# Connectors.net
KiCad netlist of a schematic drawn in Altium Designer
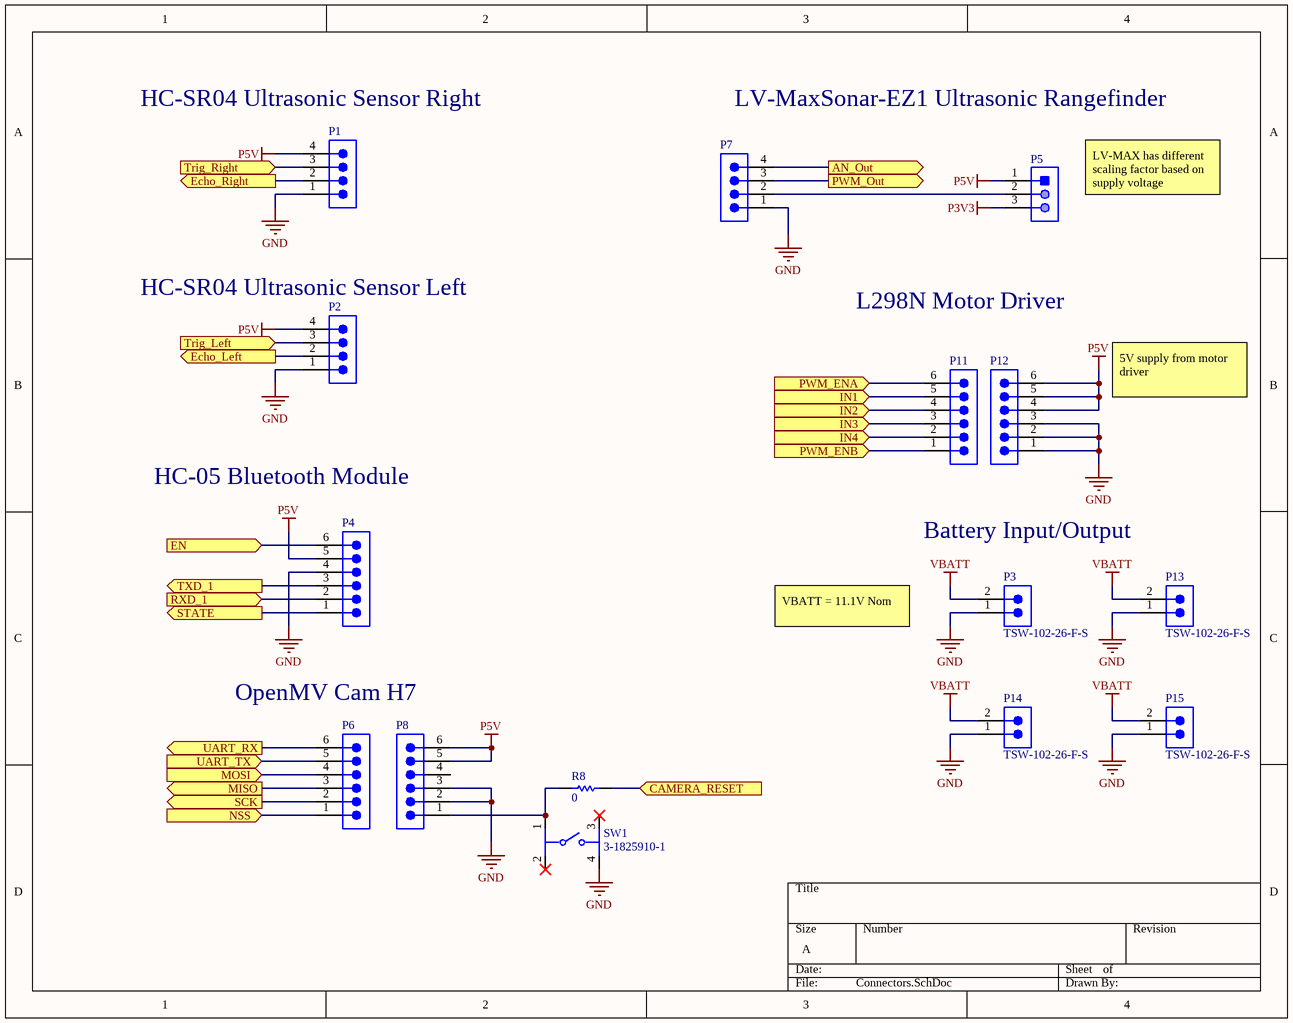
[diagram p0: Connectors.SchDoc]

(export (version "E")
  (design (tool "Eeschema 10.0.6"))
  (components
    (comp (ref "P1")
      (value "TSW-104-08-T-S")
      (footprint "SMTC-TSW-104-08-X-S")
      (description "0.025\" SQ Post Header, Through-hole, Vertical, -55 to 105 degC, 2.54 mm Pitch, 4-Pin, Male, RoHS")
      (fields (field (name "MANUFACTURER") "Samtec"))
      (libsource (lib "Altium Content Vault") (part "SMTC-TSW-104-08-X-S"))
    )
    (comp (ref "P2")
      (value "TSW-104-08-T-S")
      (footprint "SMTC-TSW-104-08-X-S")
      (description "0.025\" SQ Post Header, Through-hole, Vertical, -55 to 105 degC, 2.54 mm Pitch, 4-Pin, Male, RoHS")
      (fields (field (name "MANUFACTURER") "Samtec"))
      (libsource (lib "Altium Content Vault") (part "SMTC-TSW-104-08-X-S"))
    )
    (comp (ref "P3")
      (value "TSW-102-26-F-S")
      (footprint "SMTC-TSW-102-26-XX-S")
      (description "Headers & Wire Housings Classic PCB Header Strips, 0.100 pitch")
      (libsource (lib "University of California Riverside - FSAE") (part "SMTC-TSW-102-X-X-S-X"))
    )
    (comp (ref "P4")
      (value "TSW-106-23-G-S")
      (footprint "SMTC-TSW-106-23-X-S")
      (description "0.025\" SQ Post Header, Through-hole, Vertical, -55 to 125 degC, 2.54 mm Pitch, 6-Pin, Male, RoHS")
      (fields (field (name "MANUFACTURER") "Samtec"))
      (libsource (lib "Altium Content Vault") (part "SMTC-TSW-106-X-X-S-X"))
    )
    (comp (ref "P5")
      (value "87224-3")
      (footprint "TECO-87224-3_V")
      (fields (field (name "MANUFACTURER") "TE Connectivity"))
      (libsource (lib "Altium Content Vault") (part "CN-1P-M-R3"))
    )
    (comp (ref "P6")
      (value "TSW-106-23-G-S")
      (footprint "SMTC-TSW-106-23-X-S")
      (description "0.025\" SQ Post Header, Through-hole, Vertical, -55 to 125 degC, 2.54 mm Pitch, 6-Pin, Male, RoHS")
      (fields (field (name "MANUFACTURER") "Samtec"))
      (libsource (lib "Altium Content Vault") (part "SMTC-TSW-106-X-X-S-X"))
    )
    (comp (ref "P7")
      (value "TSW-104-08-T-S")
      (footprint "SMTC-TSW-104-08-X-S")
      (description "0.025\" SQ Post Header, Through-hole, Vertical, -55 to 105 degC, 2.54 mm Pitch, 4-Pin, Male, RoHS")
      (fields (field (name "MANUFACTURER") "Samtec"))
      (libsource (lib "Altium Content Vault") (part "SMTC-TSW-104-08-X-S"))
    )
    (comp (ref "P8")
      (value "TSW-106-23-G-S")
      (footprint "SMTC-TSW-106-23-X-S")
      (description "0.025\" SQ Post Header, Through-hole, Vertical, -55 to 125 degC, 2.54 mm Pitch, 6-Pin, Male, RoHS")
      (fields (field (name "MANUFACTURER") "Samtec"))
      (libsource (lib "Altium Content Vault") (part "SMTC-TSW-106-X-X-S-X"))
    )
    (comp (ref "P11")
      (value "TSW-106-23-G-S")
      (footprint "SMTC-TSW-106-23-X-S")
      (description "0.025\" SQ Post Header, Through-hole, Vertical, -55 to 125 degC, 2.54 mm Pitch, 6-Pin, Male, RoHS")
      (fields (field (name "MANUFACTURER") "Samtec"))
      (libsource (lib "Altium Content Vault") (part "SMTC-TSW-106-X-X-S-X"))
    )
    (comp (ref "P12")
      (value "TSW-106-23-G-S")
      (footprint "SMTC-TSW-106-23-X-S")
      (description "0.025\" SQ Post Header, Through-hole, Vertical, -55 to 125 degC, 2.54 mm Pitch, 6-Pin, Male, RoHS")
      (fields (field (name "MANUFACTURER") "Samtec"))
      (libsource (lib "Altium Content Vault") (part "SMTC-TSW-106-X-X-S-X"))
    )
    (comp (ref "P13")
      (value "TSW-102-26-F-S")
      (footprint "SMTC-TSW-102-26-XX-S")
      (description "Headers & Wire Housings Classic PCB Header Strips, 0.100 pitch")
      (libsource (lib "University of California Riverside - FSAE") (part "SMTC-TSW-102-X-X-S-X"))
    )
    (comp (ref "P14")
      (value "TSW-102-26-F-S")
      (footprint "SMTC-TSW-102-26-XX-S")
      (description "Headers & Wire Housings Classic PCB Header Strips, 0.100 pitch")
      (libsource (lib "University of California Riverside - FSAE") (part "SMTC-TSW-102-X-X-S-X"))
    )
    (comp (ref "P15")
      (value "TSW-102-26-F-S")
      (footprint "SMTC-TSW-102-26-XX-S")
      (description "Headers & Wire Housings Classic PCB Header Strips, 0.100 pitch")
      (libsource (lib "University of California Riverside - FSAE") (part "SMTC-TSW-102-X-X-S-X"))
    )
    (comp (ref "R8")
      (value "0")
      (footprint "RESC3216X60X45ML15T20")
      (description "Chip Resistor, 0 Ohm, +/- 5%, 0.25 W, -55 to 155 degC, 1206 (3216 Metric)")
      (fields (field (name "POWER") "250mW") (field (name "TOLERANCE") "5%"))
      (libsource (lib "University of California Riverside - FSAE") (part "RES-2"))
    )
    (comp (ref "SW1")
      (value "3-1825910-1")
      (footprint "FP-3-1825910-1-MFG")
      (description "Switch Tactile OFF (ON) SPST Round Button PC Pins 0.05A 24VDC 100000Cycles 1.57N Thru-Hole")
      (fields (field (name "MANUFACTURER") "TE Connectivity"))
      (libsource (lib "Altium Content Vault") (part "b8895f3f4cefb76e1819d2863dba89b"))
    )
  )
  (nets
    (net (code "1") (name "/AN_Out") (class "Default")
      (node (ref "P7") (pin "4") (pinfunction "4_4") (pintype "passive"))
    )
    (net (code "2") (name "/CAMERA_RESET") (class "Default")
      (node (ref "R8") (pin "2") (pinfunction "2_2") (pintype "passive"))
    )
    (net (code "3") (name "/EN") (class "Default")
      (node (ref "P4") (pin "6") (pinfunction "6_6") (pintype "passive"))
    )
    (net (code "4") (name "/Echo_Left") (class "Default")
      (node (ref "P2") (pin "2") (pinfunction "2_2") (pintype "passive"))
    )
    (net (code "5") (name "/Echo_Right") (class "Default")
      (node (ref "P1") (pin "2") (pinfunction "2_2") (pintype "passive"))
    )
    (net (code "6") (name "/IN1") (class "Default")
      (node (ref "P11") (pin "5") (pinfunction "5_5") (pintype "passive"))
    )
    (net (code "7") (name "/IN2") (class "Default")
      (node (ref "P11") (pin "4") (pinfunction "4_4") (pintype "passive"))
    )
    (net (code "8") (name "/IN3") (class "Default")
      (node (ref "P11") (pin "3") (pinfunction "3_3") (pintype "passive"))
    )
    (net (code "9") (name "/IN4") (class "Default")
      (node (ref "P11") (pin "2") (pinfunction "2_2") (pintype "passive"))
    )
    (net (code "10") (name "/MISO") (class "Default")
      (node (ref "P6") (pin "3") (pinfunction "3_3") (pintype "passive"))
    )
    (net (code "11") (name "/MOSI") (class "Default")
      (node (ref "P6") (pin "4") (pinfunction "4_4") (pintype "passive"))
    )
    (net (code "12") (name "/NSS") (class "Default")
      (node (ref "P6") (pin "1") (pinfunction "1_1") (pintype "passive"))
    )
    (net (code "13") (name "/PWM_ENA") (class "Default")
      (node (ref "P11") (pin "6") (pinfunction "6_6") (pintype "passive"))
    )
    (net (code "14") (name "/PWM_ENB") (class "Default")
      (node (ref "P11") (pin "1") (pinfunction "1_1") (pintype "passive"))
    )
    (net (code "15") (name "/PWM_Out") (class "Default")
      (node (ref "P7") (pin "3") (pinfunction "3_3") (pintype "passive"))
    )
    (net (code "16") (name "/RXD_1") (class "Default")
      (node (ref "P4") (pin "2") (pinfunction "2_2") (pintype "passive"))
    )
    (net (code "17") (name "/SCK") (class "Default")
      (node (ref "P6") (pin "2") (pinfunction "2_2") (pintype "passive"))
    )
    (net (code "18") (name "/STATE") (class "Default")
      (node (ref "P4") (pin "1") (pinfunction "1_1") (pintype "passive"))
    )
    (net (code "19") (name "/TXD_1") (class "Default")
      (node (ref "P4") (pin "3") (pinfunction "3_3") (pintype "passive"))
    )
    (net (code "20") (name "/Trig_Left") (class "Default")
      (node (ref "P2") (pin "3") (pinfunction "3_3") (pintype "passive"))
    )
    (net (code "21") (name "/Trig_Right") (class "Default")
      (node (ref "P1") (pin "3") (pinfunction "3_3") (pintype "passive"))
    )
    (net (code "22") (name "/UART_RX") (class "Default")
      (node (ref "P6") (pin "6") (pinfunction "6_6") (pintype "passive"))
    )
    (net (code "23") (name "/UART_TX") (class "Default")
      (node (ref "P6") (pin "5") (pinfunction "5_5") (pintype "passive"))
    )
    (net (code "24") (name "GND") (class "Default")
      (node (ref "P1") (pin "1") (pinfunction "1_1") (pintype "passive"))
      (node (ref "P12") (pin "1") (pinfunction "1_1") (pintype "passive"))
      (node (ref "P12") (pin "2") (pinfunction "2_2") (pintype "passive"))
      (node (ref "P12") (pin "3") (pinfunction "3_3") (pintype "passive"))
      (node (ref "P13") (pin "1") (pinfunction "1_1") (pintype "passive"))
      (node (ref "P14") (pin "1") (pinfunction "1_1") (pintype "passive"))
      (node (ref "P15") (pin "1") (pinfunction "1_1") (pintype "passive"))
      (node (ref "P2") (pin "1") (pinfunction "1_1") (pintype "passive"))
      (node (ref "P3") (pin "1") (pinfunction "1_1") (pintype "passive"))
      (node (ref "P4") (pin "4") (pinfunction "4_4") (pintype "passive"))
      (node (ref "P7") (pin "1") (pinfunction "1_1") (pintype "passive"))
      (node (ref "P8") (pin "2") (pinfunction "2_2") (pintype "passive"))
      (node (ref "P8") (pin "3") (pinfunction "3_3") (pintype "passive"))
      (node (ref "SW1") (pin "4") (pinfunction "4_4") (pintype "passive"))
    )
    (net (code "25") (name "Net-(P5-Pad2)") (class "Default")
      (node (ref "P5") (pin "2") (pinfunction "2_2") (pintype "passive"))
      (node (ref "P7") (pin "2") (pinfunction "2_2") (pintype "passive"))
    )
    (net (code "26") (name "Net-(P8-Pad1)") (class "Default")
      (node (ref "P8") (pin "1") (pinfunction "1_1") (pintype "passive"))
      (node (ref "R8") (pin "1") (pinfunction "1_1") (pintype "passive"))
      (node (ref "SW1") (pin "1") (pinfunction "1_1") (pintype "passive"))
    )
    (net (code "27") (name "P3V3") (class "Default")
      (node (ref "P5") (pin "3") (pinfunction "3_3") (pintype "passive"))
    )
    (net (code "28") (name "P5V") (class "Default")
      (node (ref "P1") (pin "4") (pinfunction "4_4") (pintype "passive"))
      (node (ref "P12") (pin "4") (pinfunction "4_4") (pintype "passive"))
      (node (ref "P12") (pin "5") (pinfunction "5_5") (pintype "passive"))
      (node (ref "P12") (pin "6") (pinfunction "6_6") (pintype "passive"))
      (node (ref "P2") (pin "4") (pinfunction "4_4") (pintype "passive"))
      (node (ref "P4") (pin "5") (pinfunction "5_5") (pintype "passive"))
      (node (ref "P5") (pin "1") (pinfunction "1_1") (pintype "passive"))
      (node (ref "P8") (pin "5") (pinfunction "5_5") (pintype "passive"))
      (node (ref "P8") (pin "6") (pinfunction "6_6") (pintype "passive"))
    )
    (net (code "29") (name "VBATT") (class "Default")
      (node (ref "P13") (pin "2") (pinfunction "2_2") (pintype "passive"))
      (node (ref "P14") (pin "2") (pinfunction "2_2") (pintype "passive"))
      (node (ref "P15") (pin "2") (pinfunction "2_2") (pintype "passive"))
      (node (ref "P3") (pin "2") (pinfunction "2_2") (pintype "passive"))
    )
    (net (code "30") (name "unconnected-(P8-Pad4)") (class "Default")
      (node (ref "P8") (pin "4") (pinfunction "4_4") (pintype "passive"))
    )
    (net (code "31") (name "unconnected-(SW1-Pad2)") (class "Default")
      (node (ref "SW1") (pin "2") (pinfunction "2_2") (pintype "passive+no_connect"))
    )
    (net (code "32") (name "unconnected-(SW1-Pad3)") (class "Default")
      (node (ref "SW1") (pin "3") (pinfunction "3_3") (pintype "passive+no_connect"))
    )
  )
)
